# MAINCONTROL.net
KiCad netlist of a schematic drawn in EAGLE
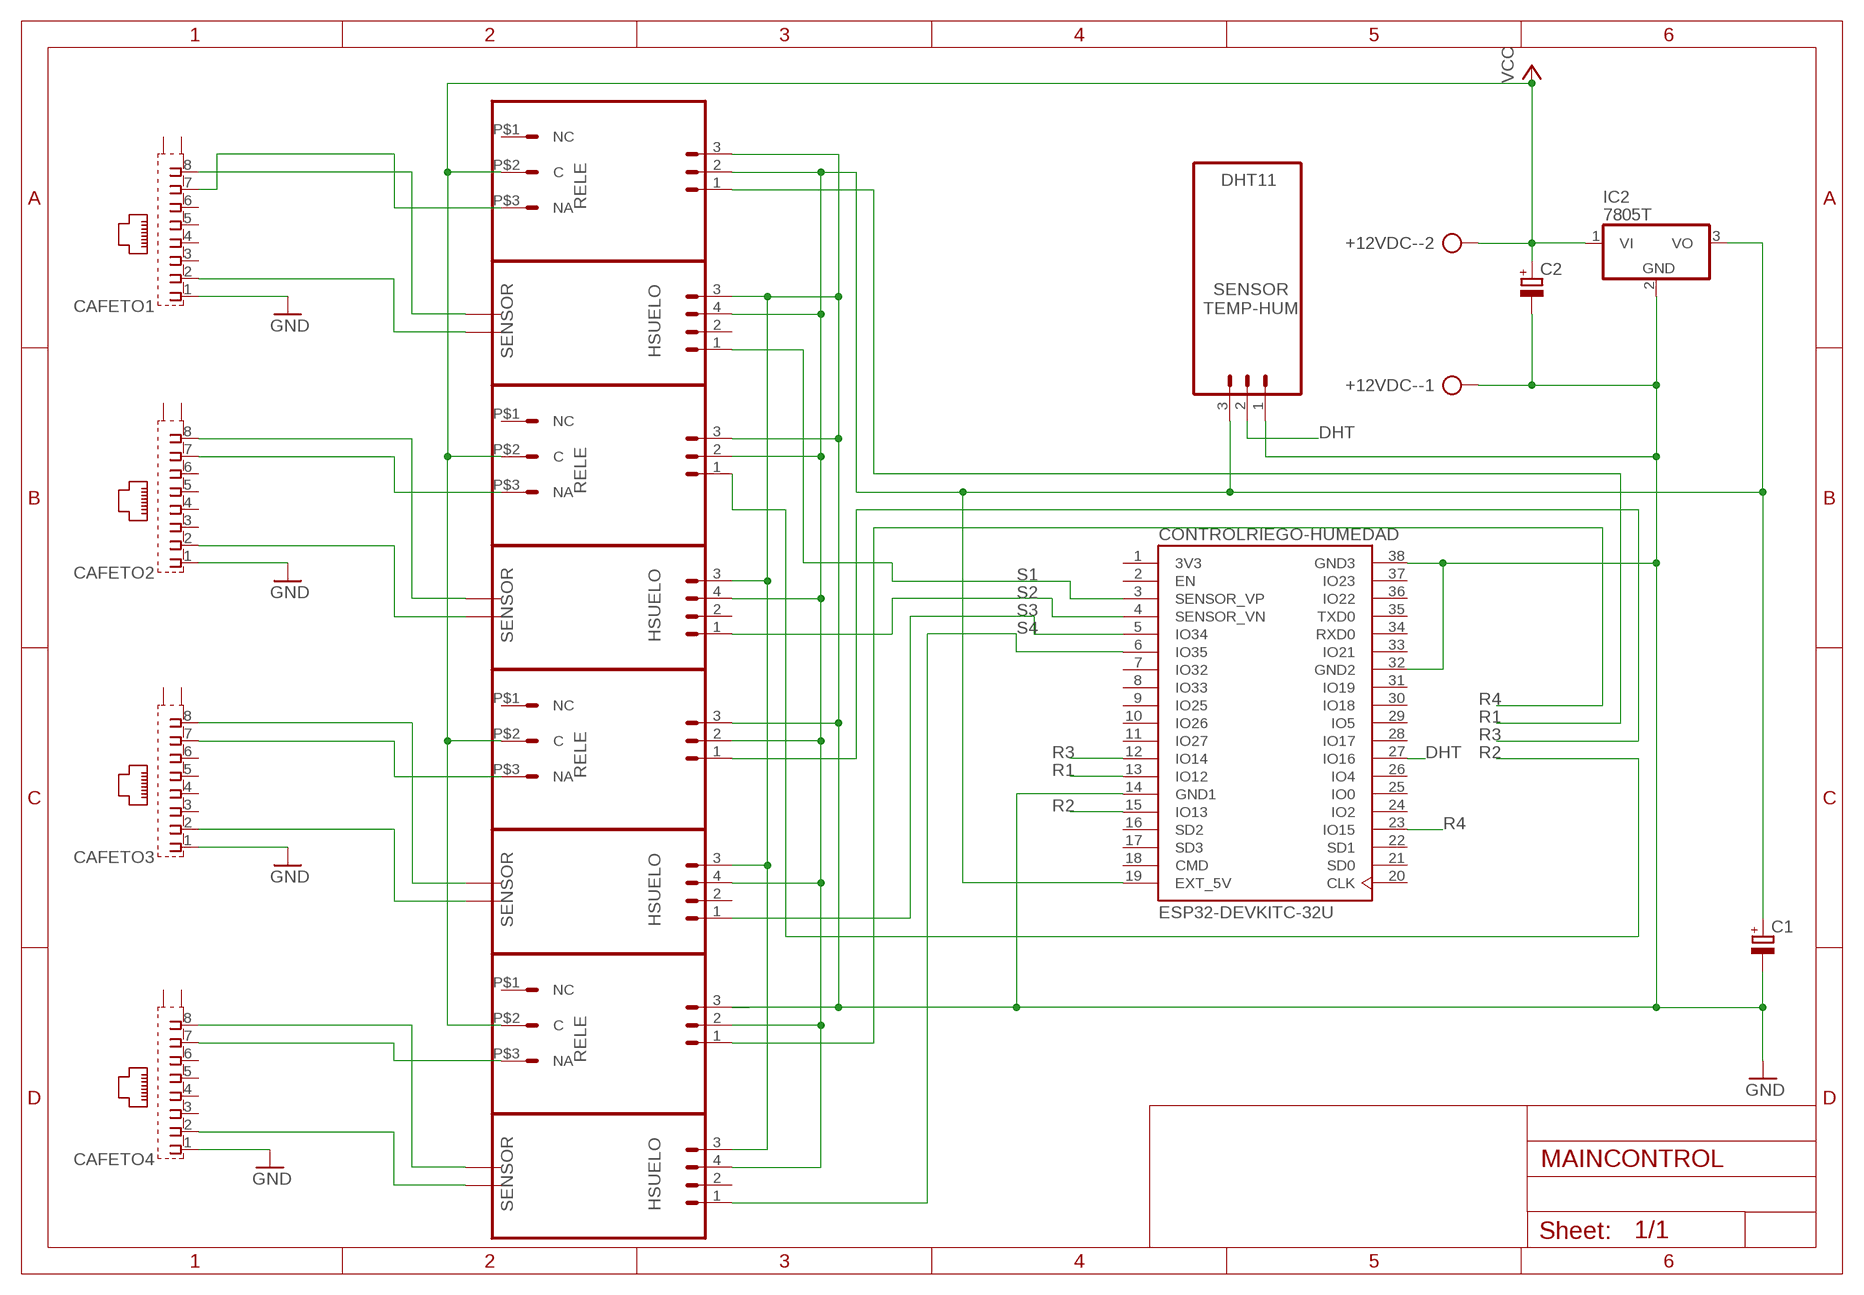
[diagram p0: schematic, sheet 1]

(export (version "E")
  (design (tool "Eeschema 10.0.6"))
  (components
    (comp (ref "+12VDC-")
      (value "AK500/2-H")
      (footprint "eagle-import:AK500_2-H")
      (libsource (lib "eagle-import") (part "AK500/2-H"))
    )
    (comp (ref "C1")
      (value "CPOL-EUE2.5-6")
      (footprint "eagle-import:E2,5-6")
      (libsource (lib "eagle-import") (part "CPOL-EUE2.5-6"))
    )
    (comp (ref "C2")
      (value "CPOL-EUE2,5-6E")
      (footprint "eagle-import:E2,5-6E")
      (libsource (lib "eagle-import") (part "CPOL-EUE2,5-6E"))
    )
    (comp (ref "CAFETO1")
      (value "RJ45-8N3-B")
      (footprint "eagle-import:TE_RJ45-8N3-B")
      (fields (field (name "COMMENT") "1-6609212-3") (field (name "MF") "TE Connectivity"))
      (libsource (lib "eagle-import") (part "RJ45-8N3-B"))
    )
    (comp (ref "CAFETO2")
      (value "RJ45-8N3-B")
      (footprint "eagle-import:TE_RJ45-8N3-B")
      (fields (field (name "COMMENT") "1-6609212-3") (field (name "MF") "TE Connectivity"))
      (libsource (lib "eagle-import") (part "RJ45-8N3-B"))
    )
    (comp (ref "CAFETO3")
      (value "RJ45-8N3-B")
      (footprint "eagle-import:TE_RJ45-8N3-B")
      (fields (field (name "COMMENT") "1-6609212-3") (field (name "MF") "TE Connectivity"))
      (libsource (lib "eagle-import") (part "RJ45-8N3-B"))
    )
    (comp (ref "CAFETO4")
      (value "RJ45-8N3-B")
      (footprint "eagle-import:TE_RJ45-8N3-B")
      (fields (field (name "COMMENT") "1-6609212-3") (field (name "MF") "TE Connectivity"))
      (libsource (lib "eagle-import") (part "RJ45-8N3-B"))
    )
    (comp (ref "CONTROLRIEGO-HUMEDAD")
      (value "ESP32-DEVKITC-32U")
      (footprint "eagle-import:MODULE_ESP32-DEVKITC-32U")
      (fields (field (name "MF") "Espressif Systems"))
      (libsource (lib "eagle-import") (part "ESP32-DEVKITC-32U"))
    )
    (comp (ref "IC2")
      (value "7805T")
      (footprint "eagle-import:TO220H")
      (libsource (lib "eagle-import") (part "78T05"))
    )
    (comp (ref "SV1")
      (value "RELE")
      (footprint "eagle-import:MA03-1")
      (libsource (lib "eagle-import") (part "RELE"))
    )
    (comp (ref "SV2")
      (value "DHT11")
      (footprint "eagle-import:DHT11")
      (libsource (lib "eagle-import") (part "DHT11"))
    )
    (comp (ref "SV3")
      (value "HSUELO")
      (footprint "eagle-import:HSUELO")
      (libsource (lib "eagle-import") (part "HSUELO"))
    )
    (comp (ref "SV4")
      (value "HSUELO")
      (footprint "eagle-import:HSUELO")
      (libsource (lib "eagle-import") (part "HSUELO"))
    )
    (comp (ref "SV5")
      (value "RELE")
      (footprint "eagle-import:MA03-1")
      (libsource (lib "eagle-import") (part "RELE"))
    )
    (comp (ref "SV6")
      (value "RELE")
      (footprint "eagle-import:MA03-1")
      (libsource (lib "eagle-import") (part "RELE"))
    )
    (comp (ref "SV7")
      (value "RELE")
      (footprint "eagle-import:MA03-1")
      (libsource (lib "eagle-import") (part "RELE"))
    )
    (comp (ref "SV8")
      (value "HSUELO")
      (footprint "eagle-import:HSUELO")
      (libsource (lib "eagle-import") (part "HSUELO"))
    )
    (comp (ref "SV9")
      (value "HSUELO")
      (footprint "eagle-import:HSUELO")
      (libsource (lib "eagle-import") (part "HSUELO"))
    )
  )
  (nets
    (net (code "1") (name "/3V3") (class "Default")
      (node (ref "CONTROLRIEGO-HUMEDAD") (pin "1") (pinfunction "3V3_1") (pintype "power_in"))
    )
    (net (code "2") (name "/DHT") (class "Default")
      (node (ref "CONTROLRIEGO-HUMEDAD") (pin "27") (pinfunction "IO16_27") (pintype "bidirectional"))
      (node (ref "SV2") (pin "2") (pinfunction "2_2") (pintype "passive"))
    )
    (net (code "3") (name "/R1") (class "Default")
      (node (ref "CONTROLRIEGO-HUMEDAD") (pin "13") (pinfunction "IO12_13") (pintype "bidirectional"))
      (node (ref "SV1") (pin "1") (pinfunction "S_1") (pintype "passive"))
    )
    (net (code "4") (name "/R2") (class "Default")
      (node (ref "CONTROLRIEGO-HUMEDAD") (pin "15") (pinfunction "IO13_15") (pintype "bidirectional"))
      (node (ref "SV5") (pin "1") (pinfunction "S_1") (pintype "passive"))
    )
    (net (code "5") (name "/R3") (class "Default")
      (node (ref "CONTROLRIEGO-HUMEDAD") (pin "12") (pinfunction "IO14_12") (pintype "bidirectional"))
      (node (ref "SV6") (pin "1") (pinfunction "S_1") (pintype "passive"))
    )
    (net (code "6") (name "/R4") (class "Default")
      (node (ref "CONTROLRIEGO-HUMEDAD") (pin "23") (pinfunction "IO15_23") (pintype "bidirectional"))
      (node (ref "SV7") (pin "1") (pinfunction "S_1") (pintype "passive"))
    )
    (net (code "7") (name "/S1") (class "Default")
      (node (ref "CONTROLRIEGO-HUMEDAD") (pin "3") (pinfunction "SENSOR_VP_3") (pintype "input"))
      (node (ref "SV8") (pin "1") (pinfunction "1_1") (pintype "passive"))
    )
    (net (code "8") (name "/S2") (class "Default")
      (node (ref "CONTROLRIEGO-HUMEDAD") (pin "4") (pinfunction "SENSOR_VN_4") (pintype "input"))
      (node (ref "SV4") (pin "1") (pinfunction "1_1") (pintype "passive"))
    )
    (net (code "9") (name "/S3") (class "Default")
      (node (ref "CONTROLRIEGO-HUMEDAD") (pin "5") (pinfunction "IO34_5") (pintype "bidirectional"))
      (node (ref "SV3") (pin "1") (pinfunction "1_1") (pintype "passive"))
    )
    (net (code "10") (name "/S4") (class "Default")
      (node (ref "CONTROLRIEGO-HUMEDAD") (pin "6") (pinfunction "IO35_6") (pintype "bidirectional"))
      (node (ref "SV9") (pin "1") (pinfunction "1_1") (pintype "passive"))
    )
    (net (code "11") (name "GND") (class "Default")
      (node (ref "+12VDC-") (pin "1") (pinfunction "KL_1") (pintype "passive"))
      (node (ref "C1") (pin "-") (pinfunction "-_-") (pintype "passive"))
      (node (ref "C2") (pin "-") (pinfunction "-_-") (pintype "passive"))
      (node (ref "CAFETO1") (pin "1") (pinfunction "1_1") (pintype "passive"))
      (node (ref "CAFETO2") (pin "1") (pinfunction "1_1") (pintype "passive"))
      (node (ref "CAFETO3") (pin "1") (pinfunction "1_1") (pintype "passive"))
      (node (ref "CAFETO4") (pin "1") (pinfunction "1_1") (pintype "passive"))
      (node (ref "CONTROLRIEGO-HUMEDAD") (pin "14") (pinfunction "GND1_14") (pintype "power_in"))
      (node (ref "CONTROLRIEGO-HUMEDAD") (pin "32") (pinfunction "GND2_32") (pintype "power_in"))
      (node (ref "CONTROLRIEGO-HUMEDAD") (pin "38") (pinfunction "GND3_38") (pintype "power_in"))
      (node (ref "IC2") (pin "2") (pinfunction "GND_2") (pintype "passive"))
      (node (ref "SV1") (pin "3") (pinfunction "GND_3") (pintype "passive"))
      (node (ref "SV2") (pin "1") (pinfunction "3_1") (pintype "passive"))
      (node (ref "SV3") (pin "3") (pinfunction "4_3") (pintype "passive"))
      (node (ref "SV4") (pin "3") (pinfunction "4_3") (pintype "passive"))
      (node (ref "SV5") (pin "3") (pinfunction "GND_3") (pintype "passive"))
      (node (ref "SV6") (pin "3") (pinfunction "GND_3") (pintype "passive"))
      (node (ref "SV7") (pin "3") (pinfunction "GND_3") (pintype "passive"))
      (node (ref "SV8") (pin "3") (pinfunction "4_3") (pintype "passive"))
      (node (ref "SV9") (pin "3") (pinfunction "4_3") (pintype "passive"))
    )
    (net (code "12") (name "Net-(CONTROLRIEGO-HUMEDAD-EXT_5V)") (class "Default")
      (node (ref "C1") (pin "+") (pinfunction "+_+") (pintype "passive"))
      (node (ref "CONTROLRIEGO-HUMEDAD") (pin "19") (pinfunction "EXT_5V_19") (pintype "power_in"))
      (node (ref "IC2") (pin "3") (pinfunction "VO_3") (pintype "passive"))
      (node (ref "SV1") (pin "2") (pinfunction "VCC_2") (pintype "passive"))
      (node (ref "SV2") (pin "3") (pinfunction "1_3") (pintype "passive"))
      (node (ref "SV3") (pin "4") (pinfunction "3_4") (pintype "passive"))
      (node (ref "SV4") (pin "4") (pinfunction "3_4") (pintype "passive"))
      (node (ref "SV5") (pin "2") (pinfunction "VCC_2") (pintype "passive"))
      (node (ref "SV6") (pin "2") (pinfunction "VCC_2") (pintype "passive"))
      (node (ref "SV7") (pin "2") (pinfunction "VCC_2") (pintype "passive"))
      (node (ref "SV8") (pin "4") (pinfunction "3_4") (pintype "passive"))
      (node (ref "SV9") (pin "4") (pinfunction "3_4") (pintype "passive"))
    )
    (net (code "13") (name "Net-(SV1-NA)") (class "Default")
      (node (ref "CAFETO1") (pin "7") (pinfunction "7_7") (pintype "passive"))
      (node (ref "SV1") (pin "P$3") (pinfunction "NA_P$3") (pintype "bidirectional"))
    )
    (net (code "14") (name "Net-(SV3-5)") (class "Default")
      (node (ref "CAFETO3") (pin "8") (pinfunction "8_8") (pintype "passive"))
      (node (ref "SV3") (pin "S1") (pinfunction "5_S1") (pintype "bidirectional"))
    )
    (net (code "15") (name "Net-(SV3-6)") (class "Default")
      (node (ref "CAFETO3") (pin "2") (pinfunction "2_2") (pintype "passive"))
      (node (ref "SV3") (pin "S2") (pinfunction "6_S2") (pintype "bidirectional"))
    )
    (net (code "16") (name "Net-(SV4-5)") (class "Default")
      (node (ref "CAFETO2") (pin "8") (pinfunction "8_8") (pintype "passive"))
      (node (ref "SV4") (pin "S1") (pinfunction "5_S1") (pintype "bidirectional"))
    )
    (net (code "17") (name "Net-(SV4-6)") (class "Default")
      (node (ref "CAFETO2") (pin "2") (pinfunction "2_2") (pintype "passive"))
      (node (ref "SV4") (pin "S2") (pinfunction "6_S2") (pintype "bidirectional"))
    )
    (net (code "18") (name "Net-(SV5-NA)") (class "Default")
      (node (ref "CAFETO2") (pin "7") (pinfunction "7_7") (pintype "passive"))
      (node (ref "SV5") (pin "P$3") (pinfunction "NA_P$3") (pintype "bidirectional"))
    )
    (net (code "19") (name "Net-(SV6-NA)") (class "Default")
      (node (ref "CAFETO3") (pin "7") (pinfunction "7_7") (pintype "passive"))
      (node (ref "SV6") (pin "P$3") (pinfunction "NA_P$3") (pintype "bidirectional"))
    )
    (net (code "20") (name "Net-(SV7-NA)") (class "Default")
      (node (ref "CAFETO4") (pin "7") (pinfunction "7_7") (pintype "passive"))
      (node (ref "SV7") (pin "P$3") (pinfunction "NA_P$3") (pintype "bidirectional"))
    )
    (net (code "21") (name "Net-(SV8-5)") (class "Default")
      (node (ref "CAFETO1") (pin "8") (pinfunction "8_8") (pintype "passive"))
      (node (ref "SV8") (pin "S1") (pinfunction "5_S1") (pintype "bidirectional"))
    )
    (net (code "22") (name "Net-(SV8-6)") (class "Default")
      (node (ref "CAFETO1") (pin "2") (pinfunction "2_2") (pintype "passive"))
      (node (ref "SV8") (pin "S2") (pinfunction "6_S2") (pintype "bidirectional"))
    )
    (net (code "23") (name "Net-(SV9-5)") (class "Default")
      (node (ref "CAFETO4") (pin "8") (pinfunction "8_8") (pintype "passive"))
      (node (ref "SV9") (pin "S1") (pinfunction "5_S1") (pintype "bidirectional"))
    )
    (net (code "24") (name "Net-(SV9-6)") (class "Default")
      (node (ref "CAFETO4") (pin "2") (pinfunction "2_2") (pintype "passive"))
      (node (ref "SV9") (pin "S2") (pinfunction "6_S2") (pintype "bidirectional"))
    )
    (net (code "25") (name "VCC") (class "Default")
      (node (ref "+12VDC-") (pin "2") (pinfunction "KL_2") (pintype "passive"))
      (node (ref "C2") (pin "+") (pinfunction "+_+") (pintype "passive"))
      (node (ref "IC2") (pin "1") (pinfunction "VI_1") (pintype "input"))
      (node (ref "SV1") (pin "P$2") (pinfunction "C_P$2") (pintype "bidirectional"))
      (node (ref "SV5") (pin "P$2") (pinfunction "C_P$2") (pintype "bidirectional"))
      (node (ref "SV6") (pin "P$2") (pinfunction "C_P$2") (pintype "bidirectional"))
      (node (ref "SV7") (pin "P$2") (pinfunction "C_P$2") (pintype "bidirectional"))
    )
    (net (code "26") (name "unconnected-(CAFETO1-Pad3)") (class "Default")
      (node (ref "CAFETO1") (pin "3") (pinfunction "3_3") (pintype "passive"))
    )
    (net (code "27") (name "unconnected-(CAFETO1-Pad4)") (class "Default")
      (node (ref "CAFETO1") (pin "4") (pinfunction "4_4") (pintype "passive"))
    )
    (net (code "28") (name "unconnected-(CAFETO1-Pad5)") (class "Default")
      (node (ref "CAFETO1") (pin "5") (pinfunction "5_5") (pintype "passive"))
    )
    (net (code "29") (name "unconnected-(CAFETO1-Pad6)") (class "Default")
      (node (ref "CAFETO1") (pin "6") (pinfunction "6_6") (pintype "passive"))
    )
    (net (code "30") (name "unconnected-(CAFETO1-S1-Pad9)") (class "Default")
      (node (ref "CAFETO1") (pin "9") (pinfunction "S1_9") (pintype "passive"))
    )
    (net (code "31") (name "unconnected-(CAFETO1-S2-Pad10)") (class "Default")
      (node (ref "CAFETO1") (pin "10") (pinfunction "S2_10") (pintype "passive"))
    )
    (net (code "32") (name "unconnected-(CAFETO2-Pad3)") (class "Default")
      (node (ref "CAFETO2") (pin "3") (pinfunction "3_3") (pintype "passive"))
    )
    (net (code "33") (name "unconnected-(CAFETO2-Pad4)") (class "Default")
      (node (ref "CAFETO2") (pin "4") (pinfunction "4_4") (pintype "passive"))
    )
    (net (code "34") (name "unconnected-(CAFETO2-Pad5)") (class "Default")
      (node (ref "CAFETO2") (pin "5") (pinfunction "5_5") (pintype "passive"))
    )
    (net (code "35") (name "unconnected-(CAFETO2-Pad6)") (class "Default")
      (node (ref "CAFETO2") (pin "6") (pinfunction "6_6") (pintype "passive"))
    )
    (net (code "36") (name "unconnected-(CAFETO2-S1-Pad9)") (class "Default")
      (node (ref "CAFETO2") (pin "9") (pinfunction "S1_9") (pintype "passive"))
    )
    (net (code "37") (name "unconnected-(CAFETO2-S2-Pad10)") (class "Default")
      (node (ref "CAFETO2") (pin "10") (pinfunction "S2_10") (pintype "passive"))
    )
    (net (code "38") (name "unconnected-(CAFETO3-Pad3)") (class "Default")
      (node (ref "CAFETO3") (pin "3") (pinfunction "3_3") (pintype "passive"))
    )
    (net (code "39") (name "unconnected-(CAFETO3-Pad4)") (class "Default")
      (node (ref "CAFETO3") (pin "4") (pinfunction "4_4") (pintype "passive"))
    )
    (net (code "40") (name "unconnected-(CAFETO3-Pad5)") (class "Default")
      (node (ref "CAFETO3") (pin "5") (pinfunction "5_5") (pintype "passive"))
    )
    (net (code "41") (name "unconnected-(CAFETO3-Pad6)") (class "Default")
      (node (ref "CAFETO3") (pin "6") (pinfunction "6_6") (pintype "passive"))
    )
    (net (code "42") (name "unconnected-(CAFETO3-S1-Pad9)") (class "Default")
      (node (ref "CAFETO3") (pin "9") (pinfunction "S1_9") (pintype "passive"))
    )
    (net (code "43") (name "unconnected-(CAFETO3-S2-Pad10)") (class "Default")
      (node (ref "CAFETO3") (pin "10") (pinfunction "S2_10") (pintype "passive"))
    )
    (net (code "44") (name "unconnected-(CAFETO4-Pad3)") (class "Default")
      (node (ref "CAFETO4") (pin "3") (pinfunction "3_3") (pintype "passive"))
    )
    (net (code "45") (name "unconnected-(CAFETO4-Pad4)") (class "Default")
      (node (ref "CAFETO4") (pin "4") (pinfunction "4_4") (pintype "passive"))
    )
    (net (code "46") (name "unconnected-(CAFETO4-Pad5)") (class "Default")
      (node (ref "CAFETO4") (pin "5") (pinfunction "5_5") (pintype "passive"))
    )
    (net (code "47") (name "unconnected-(CAFETO4-Pad6)") (class "Default")
      (node (ref "CAFETO4") (pin "6") (pinfunction "6_6") (pintype "passive"))
    )
    (net (code "48") (name "unconnected-(CAFETO4-S1-Pad9)") (class "Default")
      (node (ref "CAFETO4") (pin "9") (pinfunction "S1_9") (pintype "passive"))
    )
    (net (code "49") (name "unconnected-(CAFETO4-S2-Pad10)") (class "Default")
      (node (ref "CAFETO4") (pin "10") (pinfunction "S2_10") (pintype "passive"))
    )
    (net (code "50") (name "unconnected-(CONTROLRIEGO-HUMEDAD-CLK-Pad20)") (class "Default")
      (node (ref "CONTROLRIEGO-HUMEDAD") (pin "20") (pinfunction "CLK_20") (pintype "input"))
    )
    (net (code "51") (name "unconnected-(CONTROLRIEGO-HUMEDAD-CMD-Pad18)") (class "Default")
      (node (ref "CONTROLRIEGO-HUMEDAD") (pin "18") (pinfunction "CMD_18") (pintype "bidirectional"))
    )
    (net (code "52") (name "unconnected-(CONTROLRIEGO-HUMEDAD-EN-Pad2)") (class "Default")
      (node (ref "CONTROLRIEGO-HUMEDAD") (pin "2") (pinfunction "EN_2") (pintype "input"))
    )
    (net (code "53") (name "unconnected-(CONTROLRIEGO-HUMEDAD-IO0-Pad25)") (class "Default")
      (node (ref "CONTROLRIEGO-HUMEDAD") (pin "25") (pinfunction "IO0_25") (pintype "bidirectional"))
    )
    (net (code "54") (name "unconnected-(CONTROLRIEGO-HUMEDAD-IO2-Pad24)") (class "Default")
      (node (ref "CONTROLRIEGO-HUMEDAD") (pin "24") (pinfunction "IO2_24") (pintype "bidirectional"))
    )
    (net (code "55") (name "unconnected-(CONTROLRIEGO-HUMEDAD-IO4-Pad26)") (class "Default")
      (node (ref "CONTROLRIEGO-HUMEDAD") (pin "26") (pinfunction "IO4_26") (pintype "bidirectional"))
    )
    (net (code "56") (name "unconnected-(CONTROLRIEGO-HUMEDAD-IO5-Pad29)") (class "Default")
      (node (ref "CONTROLRIEGO-HUMEDAD") (pin "29") (pinfunction "IO5_29") (pintype "bidirectional"))
    )
    (net (code "57") (name "unconnected-(CONTROLRIEGO-HUMEDAD-IO17-Pad28)") (class "Default")
      (node (ref "CONTROLRIEGO-HUMEDAD") (pin "28") (pinfunction "IO17_28") (pintype "bidirectional"))
    )
    (net (code "58") (name "unconnected-(CONTROLRIEGO-HUMEDAD-IO18-Pad30)") (class "Default")
      (node (ref "CONTROLRIEGO-HUMEDAD") (pin "30") (pinfunction "IO18_30") (pintype "bidirectional"))
    )
    (net (code "59") (name "unconnected-(CONTROLRIEGO-HUMEDAD-IO19-Pad31)") (class "Default")
      (node (ref "CONTROLRIEGO-HUMEDAD") (pin "31") (pinfunction "IO19_31") (pintype "bidirectional"))
    )
    (net (code "60") (name "unconnected-(CONTROLRIEGO-HUMEDAD-IO21-Pad33)") (class "Default")
      (node (ref "CONTROLRIEGO-HUMEDAD") (pin "33") (pinfunction "IO21_33") (pintype "bidirectional"))
    )
    (net (code "61") (name "unconnected-(CONTROLRIEGO-HUMEDAD-IO22-Pad36)") (class "Default")
      (node (ref "CONTROLRIEGO-HUMEDAD") (pin "36") (pinfunction "IO22_36") (pintype "bidirectional"))
    )
    (net (code "62") (name "unconnected-(CONTROLRIEGO-HUMEDAD-IO23-Pad37)") (class "Default")
      (node (ref "CONTROLRIEGO-HUMEDAD") (pin "37") (pinfunction "IO23_37") (pintype "bidirectional"))
    )
    (net (code "63") (name "unconnected-(CONTROLRIEGO-HUMEDAD-IO25-Pad9)") (class "Default")
      (node (ref "CONTROLRIEGO-HUMEDAD") (pin "9") (pinfunction "IO25_9") (pintype "bidirectional"))
    )
    (net (code "64") (name "unconnected-(CONTROLRIEGO-HUMEDAD-IO26-Pad10)") (class "Default")
      (node (ref "CONTROLRIEGO-HUMEDAD") (pin "10") (pinfunction "IO26_10") (pintype "bidirectional"))
    )
    (net (code "65") (name "unconnected-(CONTROLRIEGO-HUMEDAD-IO27-Pad11)") (class "Default")
      (node (ref "CONTROLRIEGO-HUMEDAD") (pin "11") (pinfunction "IO27_11") (pintype "bidirectional"))
    )
    (net (code "66") (name "unconnected-(CONTROLRIEGO-HUMEDAD-IO32-Pad7)") (class "Default")
      (node (ref "CONTROLRIEGO-HUMEDAD") (pin "7") (pinfunction "IO32_7") (pintype "bidirectional"))
    )
    (net (code "67") (name "unconnected-(CONTROLRIEGO-HUMEDAD-IO33-Pad8)") (class "Default")
      (node (ref "CONTROLRIEGO-HUMEDAD") (pin "8") (pinfunction "IO33_8") (pintype "bidirectional"))
    )
    (net (code "68") (name "unconnected-(CONTROLRIEGO-HUMEDAD-RXD0-Pad34)") (class "Default")
      (node (ref "CONTROLRIEGO-HUMEDAD") (pin "34") (pinfunction "RXD0_34") (pintype "input"))
    )
    (net (code "69") (name "unconnected-(CONTROLRIEGO-HUMEDAD-SD0-Pad21)") (class "Default")
      (node (ref "CONTROLRIEGO-HUMEDAD") (pin "21") (pinfunction "SD0_21") (pintype "bidirectional"))
    )
    (net (code "70") (name "unconnected-(CONTROLRIEGO-HUMEDAD-SD1-Pad22)") (class "Default")
      (node (ref "CONTROLRIEGO-HUMEDAD") (pin "22") (pinfunction "SD1_22") (pintype "bidirectional"))
    )
    (net (code "71") (name "unconnected-(CONTROLRIEGO-HUMEDAD-SD2-Pad16)") (class "Default")
      (node (ref "CONTROLRIEGO-HUMEDAD") (pin "16") (pinfunction "SD2_16") (pintype "bidirectional"))
    )
    (net (code "72") (name "unconnected-(CONTROLRIEGO-HUMEDAD-SD3-Pad17)") (class "Default")
      (node (ref "CONTROLRIEGO-HUMEDAD") (pin "17") (pinfunction "SD3_17") (pintype "bidirectional"))
    )
    (net (code "73") (name "unconnected-(CONTROLRIEGO-HUMEDAD-TXD0-Pad35)") (class "Default")
      (node (ref "CONTROLRIEGO-HUMEDAD") (pin "35") (pinfunction "TXD0_35") (pintype "output"))
    )
    (net (code "74") (name "unconnected-(SV1-NC-PadP$1)") (class "Default")
      (node (ref "SV1") (pin "P$1") (pinfunction "NC_P$1") (pintype "bidirectional"))
    )
    (net (code "75") (name "unconnected-(SV3-Pad2)") (class "Default")
      (node (ref "SV3") (pin "2") (pinfunction "2_2") (pintype "passive"))
    )
    (net (code "76") (name "unconnected-(SV4-Pad2)") (class "Default")
      (node (ref "SV4") (pin "2") (pinfunction "2_2") (pintype "passive"))
    )
    (net (code "77") (name "unconnected-(SV5-NC-PadP$1)") (class "Default")
      (node (ref "SV5") (pin "P$1") (pinfunction "NC_P$1") (pintype "bidirectional"))
    )
    (net (code "78") (name "unconnected-(SV6-NC-PadP$1)") (class "Default")
      (node (ref "SV6") (pin "P$1") (pinfunction "NC_P$1") (pintype "bidirectional"))
    )
    (net (code "79") (name "unconnected-(SV7-NC-PadP$1)") (class "Default")
      (node (ref "SV7") (pin "P$1") (pinfunction "NC_P$1") (pintype "bidirectional"))
    )
    (net (code "80") (name "unconnected-(SV8-Pad2)") (class "Default")
      (node (ref "SV8") (pin "2") (pinfunction "2_2") (pintype "passive"))
    )
    (net (code "81") (name "unconnected-(SV9-Pad2)") (class "Default")
      (node (ref "SV9") (pin "2") (pinfunction "2_2") (pintype "passive"))
    )
  )
)
